# M868pld.net
KiCad netlist of a schematic drawn in EAGLE
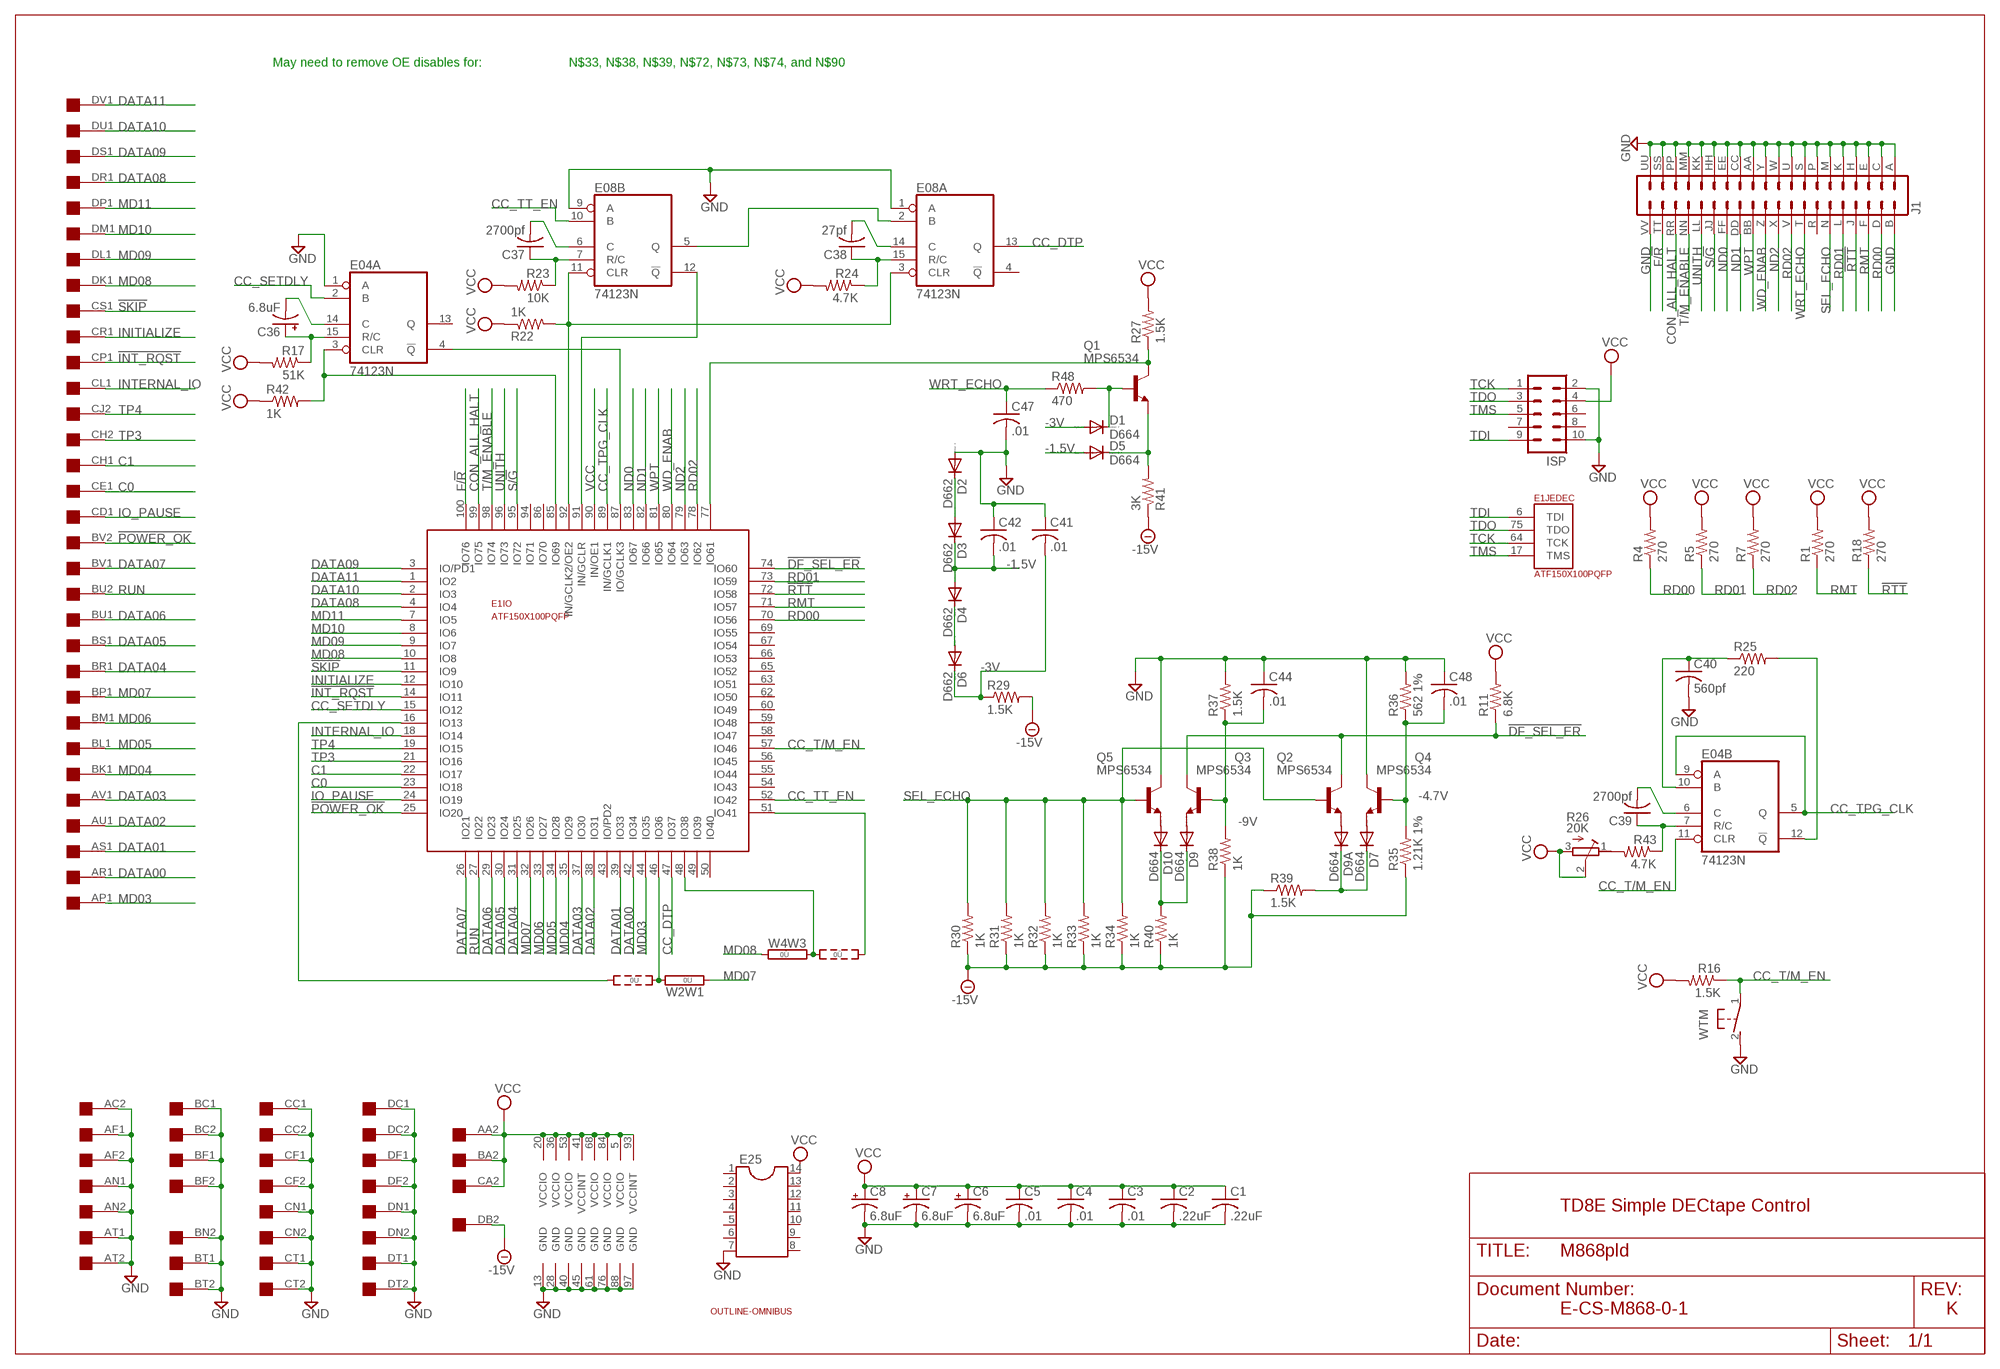
[diagram p0: schematic, sheet 1]

(export (version "E")
  (design (tool "Eeschema 10.0.6"))
  (components
    (comp (ref "C1")
      (value ".22uF")
      (footprint "eagle-import:C050-025X075")
      (libsource (lib "eagle-import") (part "C-US050-025X075"))
    )
    (comp (ref "C2")
      (value ".22uF")
      (footprint "eagle-import:C050-025X075")
      (libsource (lib "eagle-import") (part "C-US050-025X075"))
    )
    (comp (ref "C3")
      (value ".01")
      (footprint "eagle-import:C050-025X075")
      (libsource (lib "eagle-import") (part "C-US050-025X075"))
    )
    (comp (ref "C4")
      (value ".01")
      (footprint "eagle-import:C050-025X075")
      (libsource (lib "eagle-import") (part "C-US050-025X075"))
    )
    (comp (ref "C5")
      (value ".01")
      (footprint "eagle-import:C050-025X075")
      (libsource (lib "eagle-import") (part "C-US050-025X075"))
    )
    (comp (ref "C6")
      (value "6.8uF")
      (footprint "eagle-import:E12-8")
      (libsource (lib "eagle-import") (part "CPOL-USE20-8AXIAL"))
    )
    (comp (ref "C7")
      (value "6.8uF")
      (footprint "eagle-import:E12-8")
      (libsource (lib "eagle-import") (part "CPOL-USE20-8AXIAL"))
    )
    (comp (ref "C8")
      (value "6.8uF")
      (footprint "eagle-import:E12-8")
      (libsource (lib "eagle-import") (part "CPOL-USE20-8AXIAL"))
    )
    (comp (ref "C36")
      (value "6.8uF")
      (footprint "eagle-import:E12-8")
      (libsource (lib "eagle-import") (part "CPOL-USE20-8AXIAL"))
    )
    (comp (ref "C37")
      (value "2700pf")
      (footprint "eagle-import:C102-043X133")
      (libsource (lib "eagle-import") (part "C-US102-043X133"))
    )
    (comp (ref "C38")
      (value "27pf")
      (footprint "eagle-import:C050-025X075")
      (libsource (lib "eagle-import") (part "C-US050-025X075"))
    )
    (comp (ref "C39")
      (value "2700pf")
      (footprint "eagle-import:C102-043X133")
      (libsource (lib "eagle-import") (part "C-US102-043X133"))
    )
    (comp (ref "C40")
      (value "560pf")
      (footprint "eagle-import:C075-032X103")
      (libsource (lib "eagle-import") (part "C-US075-032X103"))
    )
    (comp (ref "C41")
      (value ".01")
      (footprint "eagle-import:C050-025X075")
      (libsource (lib "eagle-import") (part "C-US050-025X075"))
    )
    (comp (ref "C42")
      (value ".01")
      (footprint "eagle-import:C050-025X075")
      (libsource (lib "eagle-import") (part "C-US050-025X075"))
    )
    (comp (ref "C44")
      (value ".01")
      (footprint "eagle-import:C050-025X075")
      (libsource (lib "eagle-import") (part "C-US050-025X075"))
    )
    (comp (ref "C47")
      (value ".01")
      (footprint "eagle-import:C050-025X075")
      (libsource (lib "eagle-import") (part "C-US050-025X075"))
    )
    (comp (ref "C48")
      (value ".01")
      (footprint "eagle-import:C050-025X075")
      (libsource (lib "eagle-import") (part "C-US050-025X075"))
    )
    (comp (ref "D1")
      (value "D664")
      (footprint "eagle-import:DO35-10")
      (libsource (lib "eagle-import") (part "1N4148DO35-10"))
    )
    (comp (ref "D2")
      (value "D662")
      (footprint "eagle-import:DO35-10")
      (libsource (lib "eagle-import") (part "1N4148DO35-10"))
    )
    (comp (ref "D3")
      (value "D662")
      (footprint "eagle-import:DO35-10")
      (libsource (lib "eagle-import") (part "1N4148DO35-10"))
    )
    (comp (ref "D4")
      (value "D662")
      (footprint "eagle-import:DO35-10")
      (libsource (lib "eagle-import") (part "1N4148DO35-10"))
    )
    (comp (ref "D5")
      (value "D664")
      (footprint "eagle-import:DO35-10")
      (libsource (lib "eagle-import") (part "1N4148DO35-10"))
    )
    (comp (ref "D6")
      (value "D662")
      (footprint "eagle-import:DO35-10")
      (libsource (lib "eagle-import") (part "1N4148DO35-10"))
    )
    (comp (ref "D7")
      (value "D664")
      (footprint "eagle-import:DO35-10")
      (libsource (lib "eagle-import") (part "1N4148DO35-10"))
    )
    (comp (ref "D9")
      (value "D664")
      (footprint "eagle-import:DO35-10")
      (libsource (lib "eagle-import") (part "1N4148DO35-10"))
    )
    (comp (ref "D9A")
      (value "D664")
      (footprint "eagle-import:DO35-10")
      (libsource (lib "eagle-import") (part "1N4148DO35-10"))
    )
    (comp (ref "D10")
      (value "D664")
      (footprint "eagle-import:DO35-10")
      (libsource (lib "eagle-import") (part "1N4148DO35-10"))
    )
    (comp (ref "E1")
      (value "ATF150X100PQFP")
      (footprint "eagle-import:PQFP-100")
      (libsource (lib "eagle-import") (part "ATF150X100PQFP"))
    )
    (comp (ref "E04")
      (value "74123N")
      (footprint "eagle-import:DIL16")
      (libsource (lib "eagle-import") (part "74123N"))
    )
    (comp (ref "E08")
      (value "74123N")
      (footprint "eagle-import:DIL16")
      (libsource (lib "eagle-import") (part "74123N"))
    )
    (comp (ref "E25")
      (value "DIL14")
      (footprint "eagle-import:DIL14")
      (libsource (lib "eagle-import") (part "DIL14"))
    )
    (comp (ref "EDGE$3")
      (value "QUAD")
      (footprint "eagle-import:EDGE-CON8")
      (libsource (lib "eagle-import") (part "QUAD"))
    )
    (comp (ref "ISP")
      (value "MA05-2")
      (footprint "eagle-import:MA05-2")
      (libsource (lib "eagle-import") (part "MA05-2"))
    )
    (comp (ref "J1")
      (value "DEC40PINH")
      (footprint "eagle-import:DEC40PINH")
      (libsource (lib "eagle-import") (part "DEC40PINH"))
    )
    (comp (ref "Q1")
      (value "MPS6534")
      (footprint "eagle-import:TO5")
      (libsource (lib "eagle-import") (part "2N2219"))
    )
    (comp (ref "Q2")
      (value "MPS6534")
      (footprint "eagle-import:TO5")
      (libsource (lib "eagle-import") (part "2N2219"))
    )
    (comp (ref "Q3")
      (value "MPS6534")
      (footprint "eagle-import:TO5")
      (libsource (lib "eagle-import") (part "2N2219"))
    )
    (comp (ref "Q4")
      (value "MPS6534")
      (footprint "eagle-import:TO5")
      (libsource (lib "eagle-import") (part "2N2219"))
    )
    (comp (ref "Q5")
      (value "MPS6534")
      (footprint "eagle-import:TO5")
      (libsource (lib "eagle-import") (part "2N2219"))
    )
    (comp (ref "R1")
      (value "270")
      (footprint "eagle-import:0207_10")
      (libsource (lib "eagle-import") (part "R-US_0207/10"))
    )
    (comp (ref "R4")
      (value "270")
      (footprint "eagle-import:0207_10")
      (libsource (lib "eagle-import") (part "R-US_0207/10"))
    )
    (comp (ref "R5")
      (value "270")
      (footprint "eagle-import:0207_10")
      (libsource (lib "eagle-import") (part "R-US_0207/10"))
    )
    (comp (ref "R7")
      (value "270")
      (footprint "eagle-import:0207_10")
      (libsource (lib "eagle-import") (part "R-US_0207/10"))
    )
    (comp (ref "R11")
      (value "6.8K")
      (footprint "eagle-import:0207_10")
      (libsource (lib "eagle-import") (part "R-US_0207/10"))
    )
    (comp (ref "R16")
      (value "1.5K")
      (footprint "eagle-import:0207_10")
      (libsource (lib "eagle-import") (part "R-US_0207/10"))
    )
    (comp (ref "R17")
      (value "51K")
      (footprint "eagle-import:0207_10")
      (libsource (lib "eagle-import") (part "R-US_0207/10"))
    )
    (comp (ref "R18")
      (value "270")
      (footprint "eagle-import:0207_10")
      (libsource (lib "eagle-import") (part "R-US_0207/10"))
    )
    (comp (ref "R22")
      (value "1K")
      (footprint "eagle-import:0207_10")
      (libsource (lib "eagle-import") (part "R-US_0207/10"))
    )
    (comp (ref "R23")
      (value "10K")
      (footprint "eagle-import:0207_10")
      (libsource (lib "eagle-import") (part "R-US_0207/10"))
    )
    (comp (ref "R24")
      (value "4.7K")
      (footprint "eagle-import:0207_10")
      (libsource (lib "eagle-import") (part "R-US_0207/10"))
    )
    (comp (ref "R25")
      (value "220")
      (footprint "eagle-import:0207_10")
      (libsource (lib "eagle-import") (part "R-US_0207/10"))
    )
    (comp (ref "R26")
      (value "20K")
      (footprint "eagle-import:3006Y")
      (libsource (lib "eagle-import") (part "275P"))
    )
    (comp (ref "R27")
      (value "1.5K")
      (footprint "eagle-import:0207_10")
      (libsource (lib "eagle-import") (part "R-US_0207/10"))
    )
    (comp (ref "R29")
      (value "1.5K")
      (footprint "eagle-import:0207_10")
      (libsource (lib "eagle-import") (part "R-US_0207/10"))
    )
    (comp (ref "R30")
      (value "1K")
      (footprint "eagle-import:0207_10")
      (libsource (lib "eagle-import") (part "R-US_0207/10"))
    )
    (comp (ref "R31")
      (value "1K")
      (footprint "eagle-import:0207_10")
      (libsource (lib "eagle-import") (part "R-US_0207/10"))
    )
    (comp (ref "R32")
      (value "1K")
      (footprint "eagle-import:0207_10")
      (libsource (lib "eagle-import") (part "R-US_0207/10"))
    )
    (comp (ref "R33")
      (value "1K")
      (footprint "eagle-import:0207_10")
      (libsource (lib "eagle-import") (part "R-US_0207/10"))
    )
    (comp (ref "R34")
      (value "1K")
      (footprint "eagle-import:0207_10")
      (libsource (lib "eagle-import") (part "R-US_0207/10"))
    )
    (comp (ref "R35")
      (value "1.21K 1%")
      (footprint "eagle-import:0207_15")
      (libsource (lib "eagle-import") (part "R-US_0207/15"))
    )
    (comp (ref "R36")
      (value "562 1%")
      (footprint "eagle-import:0207_15")
      (libsource (lib "eagle-import") (part "R-US_0207/15"))
    )
    (comp (ref "R37")
      (value "1.5K")
      (footprint "eagle-import:0207_10")
      (libsource (lib "eagle-import") (part "R-US_0207/10"))
    )
    (comp (ref "R38")
      (value "1K")
      (footprint "eagle-import:0207_10")
      (libsource (lib "eagle-import") (part "R-US_0207/10"))
    )
    (comp (ref "R39")
      (value "1.5K")
      (footprint "eagle-import:0207_10")
      (libsource (lib "eagle-import") (part "R-US_0207/10"))
    )
    (comp (ref "R40")
      (value "1K")
      (footprint "eagle-import:0207_10")
      (libsource (lib "eagle-import") (part "R-US_0207/10"))
    )
    (comp (ref "R41")
      (value "3K")
      (footprint "eagle-import:0207_10")
      (libsource (lib "eagle-import") (part "R-US_0207/10"))
    )
    (comp (ref "R42")
      (value "1K")
      (footprint "eagle-import:0207_10")
      (libsource (lib "eagle-import") (part "R-US_0207/10"))
    )
    (comp (ref "R43")
      (value "4.7K")
      (footprint "eagle-import:0207_10")
      (libsource (lib "eagle-import") (part "R-US_0207/10"))
    )
    (comp (ref "R48")
      (value "470")
      (footprint "eagle-import:0207_10")
      (libsource (lib "eagle-import") (part "R-US_0207/10"))
    )
    (comp (ref "U$1")
      (value "OUTLINE-OMNIBUS")
      (footprint "eagle-import:OMNIBUS")
      (libsource (lib "eagle-import") (part "OUTLINE-OMNIBUS"))
    )
    (comp (ref "W2W1")
      (value "0R2")
      (footprint "eagle-import:0R2_10")
      (libsource (lib "eagle-import") (part "0R2"))
    )
    (comp (ref "W4W3")
      (value "0R2")
      (footprint "eagle-import:0R2_10")
      (libsource (lib "eagle-import") (part "0R2"))
    )
    (comp (ref "WTM")
      (value "31-XX")
      (footprint "eagle-import:B3F-31XX")
      (fields (field (name "MPN") "B3F-3100"))
      (libsource (lib "eagle-import") (part "31-XX"))
    )
  )
  (nets
    (net (code "1") (name "-15V") (class "Default")
      (node (ref "EDGE$3") (pin "DB2") (pinfunction "1_DB2") (pintype "bidirectional"))
      (node (ref "R29") (pin "2") (pinfunction "2_2") (pintype "passive"))
      (node (ref "R30") (pin "1") (pinfunction "1_1") (pintype "passive"))
      (node (ref "R31") (pin "1") (pinfunction "1_1") (pintype "passive"))
      (node (ref "R32") (pin "1") (pinfunction "1_1") (pintype "passive"))
      (node (ref "R33") (pin "1") (pinfunction "1_1") (pintype "passive"))
      (node (ref "R34") (pin "1") (pinfunction "1_1") (pintype "passive"))
      (node (ref "R35") (pin "1") (pinfunction "1_1") (pintype "passive"))
      (node (ref "R38") (pin "1") (pinfunction "1_1") (pintype "passive"))
      (node (ref "R39") (pin "1") (pinfunction "1_1") (pintype "passive"))
      (node (ref "R40") (pin "1") (pinfunction "1_1") (pintype "passive"))
      (node (ref "R41") (pin "1") (pinfunction "1_1") (pintype "passive"))
    )
    (net (code "2") (name "/-1.5V") (class "Default")
      (node (ref "C42") (pin "2") (pinfunction "2_2") (pintype "passive"))
      (node (ref "D3") (pin "C") (pinfunction "C_C") (pintype "passive"))
      (node (ref "D4") (pin "A") (pinfunction "A_A") (pintype "passive"))
      (node (ref "D5") (pin "A") (pinfunction "A_A") (pintype "passive"))
    )
    (net (code "3") (name "/-3V") (class "Default")
      (node (ref "C41") (pin "2") (pinfunction "2_2") (pintype "passive"))
      (node (ref "D1") (pin "A") (pinfunction "A_A") (pintype "passive"))
      (node (ref "D6") (pin "C") (pinfunction "C_C") (pintype "passive"))
      (node (ref "R29") (pin "1") (pinfunction "1_1") (pintype "passive"))
    )
    (net (code "4") (name "/-4.7V") (class "Default")
      (node (ref "C48") (pin "2") (pinfunction "2_2") (pintype "passive"))
      (node (ref "Q4") (pin "2") (pinfunction "B_2") (pintype "passive"))
      (node (ref "R35") (pin "2") (pinfunction "2_2") (pintype "passive"))
      (node (ref "R36") (pin "1") (pinfunction "1_1") (pintype "passive"))
    )
    (net (code "5") (name "/-9V") (class "Default")
      (node (ref "C44") (pin "2") (pinfunction "2_2") (pintype "passive"))
      (node (ref "Q3") (pin "2") (pinfunction "B_2") (pintype "passive"))
      (node (ref "R37") (pin "1") (pinfunction "1_1") (pintype "passive"))
      (node (ref "R38") (pin "2") (pinfunction "2_2") (pintype "passive"))
    )
    (net (code "6") (name "/C0") (class "Default")
      (node (ref "E1") (pin "23") (pinfunction "IO18_23") (pintype "bidirectional"))
      (node (ref "EDGE$3") (pin "CE1") (pinfunction "1_CE1") (pintype "bidirectional"))
    )
    (net (code "7") (name "/C1") (class "Default")
      (node (ref "E1") (pin "22") (pinfunction "IO17_22") (pintype "bidirectional"))
      (node (ref "EDGE$3") (pin "CH1") (pinfunction "1_CH1") (pintype "bidirectional"))
    )
    (net (code "8") (name "/CC_DTP") (class "Default")
      (node (ref "E08") (pin "13") (pinfunction "Q_13") (pintype "output"))
      (node (ref "E1") (pin "47") (pinfunction "IO37_47") (pintype "bidirectional"))
    )
    (net (code "9") (name "/CC_SETDLY") (class "Default")
      (node (ref "E04") (pin "2") (pinfunction "B_2") (pintype "input"))
      (node (ref "E1") (pin "15") (pinfunction "IO12_15") (pintype "bidirectional"))
    )
    (net (code "10") (name "/CC_TPG_CLK") (class "Default")
      (node (ref "E04") (pin "5") (pinfunction "Q_5") (pintype "output"))
      (node (ref "E04") (pin "9") (pinfunction "A_9") (pintype "input"))
      (node (ref "E1") (pin "89") (pinfunction "IN/GCLK1_89") (pintype "input"))
    )
    (net (code "11") (name "/CC_TT_EN") (class "Default")
      (node (ref "E08") (pin "10") (pinfunction "B_10") (pintype "input"))
      (node (ref "E1") (pin "52") (pinfunction "IO42_52") (pintype "bidirectional"))
    )
    (net (code "12") (name "/CC_T{slash}M_EN") (class "Default")
      (node (ref "E04") (pin "11") (pinfunction "CLR_11") (pintype "input"))
      (node (ref "E1") (pin "57") (pinfunction "IO46_57") (pintype "bidirectional"))
      (node (ref "R16") (pin "1") (pinfunction "1_1") (pintype "passive"))
      (node (ref "WTM") (pin "1") (pinfunction "P_1") (pintype "passive"))
    )
    (net (code "13") (name "/CON_ALL_HALT") (class "Default")
      (node (ref "E1") (pin "99") (pinfunction "IO75_99") (pintype "bidirectional"))
      (node (ref "J1") (pin "RR") (pinfunction "36_RR") (pintype "bidirectional"))
    )
    (net (code "14") (name "/DATA00") (class "Default")
      (node (ref "E1") (pin "42") (pinfunction "IO34_42") (pintype "bidirectional"))
      (node (ref "EDGE$3") (pin "AR1") (pinfunction "1_AR1") (pintype "bidirectional"))
    )
    (net (code "15") (name "/DATA01") (class "Default")
      (node (ref "E1") (pin "39") (pinfunction "IO33_39") (pintype "bidirectional"))
      (node (ref "EDGE$3") (pin "AS1") (pinfunction "1_AS1") (pintype "bidirectional"))
    )
    (net (code "16") (name "/DATA02") (class "Default")
      (node (ref "E1") (pin "38") (pinfunction "IO31_38") (pintype "bidirectional"))
      (node (ref "EDGE$3") (pin "AU1") (pinfunction "1_AU1") (pintype "bidirectional"))
    )
    (net (code "17") (name "/DATA03") (class "Default")
      (node (ref "E1") (pin "37") (pinfunction "IO30_37") (pintype "bidirectional"))
      (node (ref "EDGE$3") (pin "AV1") (pinfunction "1_AV1") (pintype "bidirectional"))
    )
    (net (code "18") (name "/DATA04") (class "Default")
      (node (ref "E1") (pin "31") (pinfunction "IO25_31") (pintype "bidirectional"))
      (node (ref "EDGE$3") (pin "BR1") (pinfunction "1_BR1") (pintype "bidirectional"))
    )
    (net (code "19") (name "/DATA05") (class "Default")
      (node (ref "E1") (pin "30") (pinfunction "IO24_30") (pintype "bidirectional"))
      (node (ref "EDGE$3") (pin "BS1") (pinfunction "1_BS1") (pintype "bidirectional"))
    )
    (net (code "20") (name "/DATA06") (class "Default")
      (node (ref "E1") (pin "29") (pinfunction "IO23_29") (pintype "bidirectional"))
      (node (ref "EDGE$3") (pin "BU1") (pinfunction "1_BU1") (pintype "bidirectional"))
    )
    (net (code "21") (name "/DATA07") (class "Default")
      (node (ref "E1") (pin "26") (pinfunction "IO21_26") (pintype "bidirectional"))
      (node (ref "EDGE$3") (pin "BV1") (pinfunction "1_BV1") (pintype "bidirectional"))
    )
    (net (code "22") (name "/DATA08") (class "Default")
      (node (ref "E1") (pin "4") (pinfunction "IO4_4") (pintype "bidirectional"))
      (node (ref "EDGE$3") (pin "DR1") (pinfunction "1_DR1") (pintype "bidirectional"))
    )
    (net (code "23") (name "/DATA09") (class "Default")
      (node (ref "E1") (pin "3") (pinfunction "IO/PD1_3") (pintype "bidirectional"))
      (node (ref "EDGE$3") (pin "DS1") (pinfunction "1_DS1") (pintype "bidirectional"))
    )
    (net (code "24") (name "/DATA10") (class "Default")
      (node (ref "E1") (pin "2") (pinfunction "IO3_2") (pintype "bidirectional"))
      (node (ref "EDGE$3") (pin "DU1") (pinfunction "1_DU1") (pintype "bidirectional"))
    )
    (net (code "25") (name "/DATA11") (class "Default")
      (node (ref "E1") (pin "1") (pinfunction "IO2_1") (pintype "bidirectional"))
      (node (ref "EDGE$3") (pin "DV1") (pinfunction "1_DV1") (pintype "bidirectional"))
    )
    (net (code "26") (name "/F{slash}~{R}") (class "Default")
      (node (ref "E1") (pin "100") (pinfunction "IO76_100") (pintype "bidirectional"))
      (node (ref "J1") (pin "TT") (pinfunction "38_TT") (pintype "bidirectional"))
    )
    (net (code "27") (name "/INITIALIZE") (class "Default")
      (node (ref "E1") (pin "12") (pinfunction "IO10_12") (pintype "bidirectional"))
      (node (ref "EDGE$3") (pin "CR1") (pinfunction "1_CR1") (pintype "bidirectional"))
    )
    (net (code "28") (name "/INTERNAL_IO") (class "Default")
      (node (ref "E1") (pin "18") (pinfunction "IO14_18") (pintype "bidirectional"))
      (node (ref "EDGE$3") (pin "CL1") (pinfunction "1_CL1") (pintype "bidirectional"))
    )
    (net (code "29") (name "/IO_PAUSE") (class "Default")
      (node (ref "E1") (pin "24") (pinfunction "IO19_24") (pintype "bidirectional"))
      (node (ref "EDGE$3") (pin "CD1") (pinfunction "1_CD1") (pintype "bidirectional"))
    )
    (net (code "30") (name "/MD03") (class "Default")
      (node (ref "E1") (pin "44") (pinfunction "IO35_44") (pintype "bidirectional"))
      (node (ref "EDGE$3") (pin "AP1") (pinfunction "1_AP1") (pintype "bidirectional"))
    )
    (net (code "31") (name "/MD04") (class "Default")
      (node (ref "E1") (pin "35") (pinfunction "IO29_35") (pintype "bidirectional"))
      (node (ref "EDGE$3") (pin "BK1") (pinfunction "1_BK1") (pintype "bidirectional"))
    )
    (net (code "32") (name "/MD05") (class "Default")
      (node (ref "E1") (pin "34") (pinfunction "IO28_34") (pintype "bidirectional"))
      (node (ref "EDGE$3") (pin "BL1") (pinfunction "1_BL1") (pintype "bidirectional"))
    )
    (net (code "33") (name "/MD06") (class "Default")
      (node (ref "E1") (pin "33") (pinfunction "IO27_33") (pintype "bidirectional"))
      (node (ref "EDGE$3") (pin "BM1") (pinfunction "1_BM1") (pintype "bidirectional"))
    )
    (net (code "34") (name "/MD07") (class "Default")
      (node (ref "E1") (pin "32") (pinfunction "IO26_32") (pintype "bidirectional"))
      (node (ref "EDGE$3") (pin "BP1") (pinfunction "1_BP1") (pintype "bidirectional"))
      (node (ref "W2W1") (pin "1") (pinfunction "1_1") (pintype "passive"))
    )
    (net (code "35") (name "/MD08") (class "Default")
      (node (ref "E1") (pin "10") (pinfunction "IO8_10") (pintype "bidirectional"))
      (node (ref "EDGE$3") (pin "DK1") (pinfunction "1_DK1") (pintype "bidirectional"))
      (node (ref "W4W3") (pin "1") (pinfunction "1_1") (pintype "passive"))
    )
    (net (code "36") (name "/MD09") (class "Default")
      (node (ref "E1") (pin "9") (pinfunction "IO7_9") (pintype "bidirectional"))
      (node (ref "EDGE$3") (pin "DL1") (pinfunction "1_DL1") (pintype "bidirectional"))
    )
    (net (code "37") (name "/MD10") (class "Default")
      (node (ref "E1") (pin "8") (pinfunction "IO6_8") (pintype "bidirectional"))
      (node (ref "EDGE$3") (pin "DM1") (pinfunction "1_DM1") (pintype "bidirectional"))
    )
    (net (code "38") (name "/MD11") (class "Default")
      (node (ref "E1") (pin "7") (pinfunction "IO5_7") (pintype "bidirectional"))
      (node (ref "EDGE$3") (pin "DP1") (pinfunction "1_DP1") (pintype "bidirectional"))
    )
    (net (code "39") (name "/ND0") (class "Default")
      (node (ref "E1") (pin "83") (pinfunction "IO67_83") (pintype "bidirectional"))
      (node (ref "J1") (pin "FF") (pinfunction "28_FF") (pintype "bidirectional"))
    )
    (net (code "40") (name "/ND1") (class "Default")
      (node (ref "E1") (pin "82") (pinfunction "IO66_82") (pintype "bidirectional"))
      (node (ref "J1") (pin "DD") (pinfunction "26_DD") (pintype "bidirectional"))
    )
    (net (code "41") (name "/ND2") (class "Default")
      (node (ref "E1") (pin "79") (pinfunction "IO63_79") (pintype "bidirectional"))
      (node (ref "J1") (pin "X") (pinfunction "20_X") (pintype "bidirectional"))
    )
    (net (code "42") (name "/RD00") (class "Default")
      (node (ref "E1") (pin "70") (pinfunction "IO56_70") (pintype "bidirectional"))
      (node (ref "J1") (pin "D") (pinfunction "4_D") (pintype "bidirectional"))
      (node (ref "R4") (pin "1") (pinfunction "1_1") (pintype "passive"))
    )
    (net (code "43") (name "/RD01") (class "Default")
      (node (ref "E1") (pin "73") (pinfunction "IO59_73") (pintype "bidirectional"))
      (node (ref "J1") (pin "L") (pinfunction "10_L") (pintype "bidirectional"))
      (node (ref "R5") (pin "1") (pinfunction "1_1") (pintype "passive"))
    )
    (net (code "44") (name "/RD02") (class "Default")
      (node (ref "E1") (pin "78") (pinfunction "IO62_78") (pintype "bidirectional"))
      (node (ref "J1") (pin "V") (pinfunction "18_V") (pintype "bidirectional"))
      (node (ref "R7") (pin "1") (pinfunction "1_1") (pintype "passive"))
    )
    (net (code "45") (name "/RMT") (class "Default")
      (node (ref "E1") (pin "71") (pinfunction "IO57_71") (pintype "bidirectional"))
      (node (ref "J1") (pin "F") (pinfunction "6_F") (pintype "bidirectional"))
      (node (ref "R1") (pin "1") (pinfunction "1_1") (pintype "passive"))
    )
    (net (code "46") (name "/RUN") (class "Default")
      (node (ref "E1") (pin "27") (pinfunction "IO22_27") (pintype "bidirectional"))
      (node (ref "EDGE$3") (pin "BU2") (pinfunction "1_BU2") (pintype "bidirectional"))
    )
    (net (code "47") (name "/SEL_ECHO") (class "Default")
      (node (ref "J1") (pin "N") (pinfunction "12_N") (pintype "bidirectional"))
      (node (ref "Q2") (pin "2") (pinfunction "B_2") (pintype "passive"))
      (node (ref "Q5") (pin "2") (pinfunction "B_2") (pintype "passive"))
      (node (ref "R30") (pin "2") (pinfunction "2_2") (pintype "passive"))
      (node (ref "R31") (pin "2") (pinfunction "2_2") (pintype "passive"))
      (node (ref "R32") (pin "2") (pinfunction "2_2") (pintype "passive"))
      (node (ref "R33") (pin "2") (pinfunction "2_2") (pintype "passive"))
      (node (ref "R34") (pin "2") (pinfunction "2_2") (pintype "passive"))
    )
    (net (code "48") (name "/S{slash}~{G}") (class "Default")
      (node (ref "E1") (pin "95") (pinfunction "IO72_95") (pintype "bidirectional"))
      (node (ref "J1") (pin "JJ") (pinfunction "30_JJ") (pintype "bidirectional"))
    )
    (net (code "49") (name "/TCK") (class "Default")
      (node (ref "E1") (pin "64") (pinfunction "TCK_64") (pintype "bidirectional"))
      (node (ref "ISP") (pin "1") (pinfunction "1_1") (pintype "passive"))
    )
    (net (code "50") (name "/TDI") (class "Default")
      (node (ref "E1") (pin "6") (pinfunction "TDI_6") (pintype "bidirectional"))
      (node (ref "ISP") (pin "9") (pinfunction "9_9") (pintype "passive"))
    )
    (net (code "51") (name "/TDO") (class "Default")
      (node (ref "E1") (pin "75") (pinfunction "TDO_75") (pintype "bidirectional"))
      (node (ref "ISP") (pin "3") (pinfunction "3_3") (pintype "passive"))
    )
    (net (code "52") (name "/TMS") (class "Default")
      (node (ref "E1") (pin "17") (pinfunction "TMS_17") (pintype "bidirectional"))
      (node (ref "ISP") (pin "5") (pinfunction "5_5") (pintype "passive"))
    )
    (net (code "53") (name "/TP3") (class "Default")
      (node (ref "E1") (pin "21") (pinfunction "IO16_21") (pintype "bidirectional"))
      (node (ref "EDGE$3") (pin "CH2") (pinfunction "1_CH2") (pintype "bidirectional"))
    )
    (net (code "54") (name "/TP4") (class "Default")
      (node (ref "E1") (pin "19") (pinfunction "IO15_19") (pintype "bidirectional"))
      (node (ref "EDGE$3") (pin "CJ2") (pinfunction "1_CJ2") (pintype "bidirectional"))
    )
    (net (code "55") (name "/T{slash}M_ENABLE") (class "Default")
      (node (ref "E1") (pin "98") (pinfunction "IO74_98") (pintype "bidirectional"))
      (node (ref "J1") (pin "NN") (pinfunction "34_NN") (pintype "bidirectional"))
    )
    (net (code "56") (name "/UNITH") (class "Default")
      (node (ref "E1") (pin "96") (pinfunction "IO73_96") (pintype "bidirectional"))
      (node (ref "J1") (pin "LL") (pinfunction "32_LL") (pintype "bidirectional"))
    )
    (net (code "57") (name "/WD_ENAB") (class "Default")
      (node (ref "E1") (pin "80") (pinfunction "IO64_80") (pintype "bidirectional"))
      (node (ref "J1") (pin "Z") (pinfunction "22_Z") (pintype "bidirectional"))
    )
    (net (code "58") (name "/WPT") (class "Default")
      (node (ref "E1") (pin "81") (pinfunction "IO65_81") (pintype "bidirectional"))
      (node (ref "J1") (pin "BB") (pinfunction "24_BB") (pintype "bidirectional"))
    )
    (net (code "59") (name "/WRT_ECHO") (class "Default")
      (node (ref "C47") (pin "1") (pinfunction "1_1") (pintype "passive"))
      (node (ref "J1") (pin "T") (pinfunction "16_T") (pintype "bidirectional"))
      (node (ref "R48") (pin "1") (pinfunction "1_1") (pintype "passive"))
    )
    (net (code "60") (name "/~{DF_SEL_ER}") (class "Default")
      (node (ref "E1") (pin "74") (pinfunction "IO60_74") (pintype "bidirectional"))
      (node (ref "Q2") (pin "3") (pinfunction "C_3") (pintype "passive"))
      (node (ref "Q3") (pin "3") (pinfunction "C_3") (pintype "passive"))
      (node (ref "R11") (pin "1") (pinfunction "1_1") (pintype "passive"))
    )
    (net (code "61") (name "/~{INT_RQST}") (class "Default")
      (node (ref "E1") (pin "14") (pinfunction "IO11_14") (pintype "bidirectional"))
      (node (ref "EDGE$3") (pin "CP1") (pinfunction "1_CP1") (pintype "bidirectional"))
    )
    (net (code "62") (name "/~{POWER_OK}") (class "Default")
      (node (ref "E1") (pin "25") (pinfunction "IO20_25") (pintype "bidirectional"))
      (node (ref "EDGE$3") (pin "BV2") (pinfunction "1_BV2") (pintype "bidirectional"))
    )
    (net (code "63") (name "/~{RTT}") (class "Default")
      (node (ref "E1") (pin "72") (pinfunction "IO58_72") (pintype "bidirectional"))
      (node (ref "J1") (pin "J") (pinfunction "8_J") (pintype "bidirectional"))
      (node (ref "R18") (pin "1") (pinfunction "1_1") (pintype "passive"))
    )
    (net (code "64") (name "/~{SKIP}") (class "Default")
      (node (ref "E1") (pin "11") (pinfunction "IO9_11") (pintype "bidirectional"))
      (node (ref "EDGE$3") (pin "CS1") (pinfunction "1_CS1") (pintype "bidirectional"))
    )
    (net (code "65") (name "GND") (class "Default")
      (node (ref "C1") (pin "2") (pinfunction "2_2") (pintype "passive"))
      (node (ref "C2") (pin "2") (pinfunction "2_2") (pintype "passive"))
      (node (ref "C3") (pin "2") (pinfunction "2_2") (pintype "passive"))
      (node (ref "C4") (pin "2") (pinfunction "2_2") (pintype "passive"))
      (node (ref "C40") (pin "2") (pinfunction "2_2") (pintype "passive"))
      (node (ref "C41") (pin "1") (pinfunction "1_1") (pintype "passive"))
      (node (ref "C42") (pin "1") (pinfunction "1_1") (pintype "passive"))
      (node (ref "C44") (pin "1") (pinfunction "1_1") (pintype "passive"))
      (node (ref "C47") (pin "2") (pinfunction "2_2") (pintype "passive"))
      (node (ref "C48") (pin "1") (pinfunction "1_1") (pintype "passive"))
      (node (ref "C5") (pin "2") (pinfunction "2_2") (pintype "passive"))
      (node (ref "C6") (pin "-") (pinfunction "-_-") (pintype "passive"))
      (node (ref "C7") (pin "-") (pinfunction "-_-") (pintype "passive"))
      (node (ref "C8") (pin "-") (pinfunction "-_-") (pintype "passive"))
      (node (ref "D2") (pin "A") (pinfunction "A_A") (pintype "passive"))
      (node (ref "E04") (pin "1") (pinfunction "A_1") (pintype "input"))
      (node (ref "E08") (pin "1") (pinfunction "A_1") (pintype "input"))
      (node (ref "E08") (pin "9") (pinfunction "A_9") (pintype "input"))
      (node (ref "E1") (pin "13") (pinfunction "GND_13") (pintype "power_in"))
      (node (ref "E1") (pin "28") (pinfunction "GND_28") (pintype "power_in"))
      (node (ref "E1") (pin "40") (pinfunction "GND_40") (pintype "power_in"))
      (node (ref "E1") (pin "45") (pinfunction "GND_45") (pintype "power_in"))
      (node (ref "E1") (pin "61") (pinfunction "GND_61") (pintype "power_in"))
      (node (ref "E1") (pin "76") (pinfunction "GND_76") (pintype "power_in"))
      (node (ref "E1") (pin "88") (pinfunction "GND_88") (pintype "power_in"))
      (node (ref "E1") (pin "97") (pinfunction "GND_97") (pintype "power_in"))
      (node (ref "E25") (pin "7") (pinfunction "7_7") (pintype "passive"))
      (node (ref "EDGE$3") (pin "AC2") (pinfunction "1_AC2") (pintype "bidirectional"))
      (node (ref "EDGE$3") (pin "AF1") (pinfunction "1_AF1") (pintype "bidirectional"))
      (node (ref "EDGE$3") (pin "AF2") (pinfunction "1_AF2") (pintype "bidirectional"))
      (node (ref "EDGE$3") (pin "AN1") (pinfunction "1_AN1") (pintype "bidirectional"))
      (node (ref "EDGE$3") (pin "AN2") (pinfunction "1_AN2") (pintype "bidirectional"))
      (node (ref "EDGE$3") (pin "AT1") (pinfunction "1_AT1") (pintype "bidirectional"))
      (node (ref "EDGE$3") (pin "AT2") (pinfunction "1_AT2") (pintype "bidirectional"))
      (node (ref "EDGE$3") (pin "BC1") (pinfunction "1_BC1") (pintype "bidirectional"))
      (node (ref "EDGE$3") (pin "BC2") (pinfunction "1_BC2") (pintype "bidirectional"))
      (node (ref "EDGE$3") (pin "BF1") (pinfunction "1_BF1") (pintype "bidirectional"))
      (node (ref "EDGE$3") (pin "BF2") (pinfunction "1_BF2") (pintype "bidirectional"))
      (node (ref "EDGE$3") (pin "BN2") (pinfunction "1_BN2") (pintype "bidirectional"))
      (node (ref "EDGE$3") (pin "BT1") (pinfunction "1_BT1") (pintype "bidirectional"))
      (node (ref "EDGE$3") (pin "BT2") (pinfunction "1_BT2") (pintype "bidirectional"))
      (node (ref "EDGE$3") (pin "CC1") (pinfunction "1_CC1") (pintype "bidirectional"))
      (node (ref "EDGE$3") (pin "CC2") (pinfunction "1_CC2") (pintype "bidirectional"))
      (node (ref "EDGE$3") (pin "CF1") (pinfunction "1_CF1") (pintype "bidirectional"))
      (node (ref "EDGE$3") (pin "CF2") (pinfunction "1_CF2") (pintype "bidirectional"))
      (node (ref "EDGE$3") (pin "CN1") (pinfunction "1_CN1") (pintype "bidirectional"))
      (node (ref "EDGE$3") (pin "CN2") (pinfunction "1_CN2") (pintype "bidirectional"))
      (node (ref "EDGE$3") (pin "CT1") (pinfunction "1_CT1") (pintype "bidirectional"))
      (node (ref "EDGE$3") (pin "CT2") (pinfunction "1_CT2") (pintype "bidirectional"))
      (node (ref "EDGE$3") (pin "DC1") (pinfunction "1_DC1") (pintype "bidirectional"))
      (node (ref "EDGE$3") (pin "DC2") (pinfunction "1_DC2") (pintype "bidirectional"))
      (node (ref "EDGE$3") (pin "DF1") (pinfunction "1_DF1") (pintype "bidirectional"))
      (node (ref "EDGE$3") (pin "DF2") (pinfunction "1_DF2") (pintype "bidirectional"))
      (node (ref "EDGE$3") (pin "DN1") (pinfunction "1_DN1") (pintype "bidirectional"))
      (node (ref "EDGE$3") (pin "DN2") (pinfunction "1_DN2") (pintype "bidirectional"))
      (node (ref "EDGE$3") (pin "DT1") (pinfunction "1_DT1") (pintype "bidirectional"))
      (node (ref "EDGE$3") (pin "DT2") (pinfunction "1_DT2") (pintype "bidirectional"))
      (node (ref "ISP") (pin "10") (pinfunction "10_10") (pintype "passive"))
      (node (ref "ISP") (pin "2") (pinfunction "2_2") (pintype "passive"))
      (node (ref "J1") (pin "A") (pinfunction "1_A") (pintype "bidirectional"))
      (node (ref "J1") (pin "AA") (pinfunction "23_AA") (pintype "bidirectional"))
      (node (ref "J1") (pin "B") (pinfunction "2_B") (pintype "bidirectional"))
      (node (ref "J1") (pin "C") (pinfunction "3_C") (pintype "bidirectional"))
      (node (ref "J1") (pin "CC") (pinfunction "25_CC") (pintype "bidirectional"))
      (node (ref "J1") (pin "E") (pinfunction "5_E") (pintype "bidirectional"))
      (node (ref "J1") (pin "EE") (pinfunction "27_EE") (pintype "bidirectional"))
      (node (ref "J1") (pin "H") (pinfunction "7_H") (pintype "bidirectional"))
      (node (ref "J1") (pin "HH") (pinfunction "29_HH") (pintype "bidirectional"))
      (node (ref "J1") (pin "K") (pinfunction "9_K") (pintype "bidirectional"))
      (node (ref "J1") (pin "KK") (pinfunction "31_KK") (pintype "bidirectional"))
      (node (ref "J1") (pin "M") (pinfunction "11_M") (pintype "bidirectional"))
      (node (ref "J1") (pin "MM") (pinfunction "33_MM") (pintype "bidirectional"))
      (node (ref "J1") (pin "P") (pinfunction "13_P") (pintype "bidirectional"))
      (node (ref "J1") (pin "PP") (pinfunction "35_PP") (pintype "bidirectional"))
      (node (ref "J1") (pin "S") (pinfunction "15_S") (pintype "bidirectional"))
      (node (ref "J1") (pin "SS") (pinfunction "37_SS") (pintype "bidirectional"))
      (node (ref "J1") (pin "U") (pinfunction "17_U") (pintype "bidirectional"))
      (node (ref "J1") (pin "UU") (pinfunction "39_UU") (pintype "bidirectional"))
      (node (ref "J1") (pin "VV") (pinfunction "40_VV") (pintype "bidirectional"))
      (node (ref "J1") (pin "W") (pinfunction "19_W") (pintype "bidirectional"))
      (node (ref "J1") (pin "Y") (pinfunction "21_Y") (pintype "bidirectional"))
      (node (ref "Q4") (pin "3") (pinfunction "C_3") (pintype "passive"))
      (node (ref "Q5") (pin "3") (pinfunction "C_3") (pintype "passive"))
      (node (ref "R36") (pin "2") (pinfunction "2_2") (pintype "passive"))
      (node (ref "R37") (pin "2") (pinfunction "2_2") (pintype "passive"))
      (node (ref "WTM") (pin "2") (pinfunction "S_2") (pintype "passive"))
    )
    (net (code "66") (name "Net-(D2-PadC)") (class "Default")
      (node (ref "D2") (pin "C") (pinfunction "C_C") (pintype "passive"))
      (node (ref "D3") (pin "A") (pinfunction "A_A") (pintype "passive"))
    )
    (net (code "67") (name "Net-(D4-PadC)") (class "Default")
      (node (ref "D4") (pin "C") (pinfunction "C_C") (pintype "passive"))
      (node (ref "D6") (pin "A") (pinfunction "A_A") (pintype "passive"))
    )
    (net (code "68") (name "Net-(D7-PadC)") (class "Default")
      (node (ref "D7") (pin "C") (pinfunction "C_C") (pintype "passive"))
      (node (ref "D9A") (pin "C") (pinfunction "C_C") (pintype "passive"))
      (node (ref "R39") (pin "2") (pinfunction "2_2") (pintype "passive"))
    )
    (net (code "69") (name "Net-(D10-PadC)") (class "Default")
      (node (ref "D10") (pin "C") (pinfunction "C_C") (pintype "passive"))
      (node (ref "D9") (pin "C") (pinfunction "C_C") (pintype "passive"))
      (node (ref "R40") (pin "2") (pinfunction "2_2") (pintype "passive"))
    )
    (net (code "70") (name "Net-(E1Q-IO13)") (class "Default")
      (node (ref "E1") (pin "16") (pinfunction "IO13_16") (pintype "bidirectional"))
      (node (ref "W2W1") (pin "3") (pinfunction "3_3") (pintype "passive"))
    )
    (net (code "71") (name "Net-(E1Q-IO36)") (class "Default")
      (node (ref "E1") (pin "46") (pinfunction "IO36_46") (pintype "bidirectional"))
      (node (ref "W2W1") (pin "2") (pinfunction "2_2") (pintype "passive"))
    )
    (net (code "72") (name "Net-(E1Q-IO38)") (class "Default")
      (node (ref "E1") (pin "48") (pinfunction "IO38_48") (pintype "bidirectional"))
      (node (ref "W4W3") (pin "2") (pinfunction "2_2") (pintype "passive"))
    )
    (net (code "73") (name "Net-(E1Q-IO41)") (class "Default")
      (node (ref "E1") (pin "51") (pinfunction "IO41_51") (pintype "bidirectional"))
      (node (ref "W4W3") (pin "3") (pinfunction "3_3") (pintype "passive"))
    )
    (net (code "74") (name "Net-(E1Q-IO61)") (class "Default")
      (node (ref "E1") (pin "77") (pinfunction "IO61_77") (pintype "bidirectional"))
      (node (ref "Q1") (pin "3") (pinfunction "C_3") (pintype "passive"))
      (node (ref "R27") (pin "1") (pinfunction "1_1") (pintype "passive"))
    )
    (net (code "75") (name "Net-(E04A-C)") (class "Default")
      (node (ref "C36") (pin "-") (pinfunction "-_-") (pintype "passive"))
      (node (ref "E04") (pin "14") (pinfunction "C_14") (pintype "input"))
    )
    (net (code "76") (name "Net-(E04A-CLR)") (class "Default")
      (node (ref "E04") (pin "3") (pinfunction "CLR_3") (pintype "input"))
      (node (ref "E1") (pin "85") (pinfunction "IO69_85") (pintype "bidirectional"))
      (node (ref "R42") (pin "2") (pinfunction "2_2") (pintype "passive"))
    )
    (net (code "77") (name "Net-(E04A-R{slash}C)") (class "Default")
      (node (ref "C36") (pin "+") (pinfunction "+_+") (pintype "passive"))
      (node (ref "E04") (pin "15") (pinfunction "R/C_15") (pintype "input"))
      (node (ref "R17") (pin "1") (pinfunction "1_1") (pintype "passive"))
    )
    (net (code "78") (name "Net-(E04A-~{Q})") (class "Default")
      (node (ref "E04") (pin "4") (pinfunction "~{Q}_4") (pintype "output"))
      (node (ref "E1") (pin "87") (pinfunction "IO/GCLK3_87") (pintype "bidirectional"))
    )
    (net (code "79") (name "Net-(E04B-B)") (class "Default")
      (node (ref "C40") (pin "1") (pinfunction "1_1") (pintype "passive"))
      (node (ref "E04") (pin "10") (pinfunction "B_10") (pintype "input"))
      (node (ref "R25") (pin "1") (pinfunction "1_1") (pintype "passive"))
    )
    (net (code "80") (name "Net-(E04B-C)") (class "Default")
      (node (ref "C39") (pin "2") (pinfunction "2_2") (pintype "passive"))
      (node (ref "E04") (pin "6") (pinfunction "C_6") (pintype "input"))
    )
    (net (code "81") (name "Net-(E04B-R{slash}C)") (class "Default")
      (node (ref "C39") (pin "1") (pinfunction "1_1") (pintype "passive"))
      (node (ref "E04") (pin "7") (pinfunction "R/C_7") (pintype "input"))
      (node (ref "R43") (pin "1") (pinfunction "1_1") (pintype "passive"))
    )
    (net (code "82") (name "Net-(E04B-~{Q})") (class "Default")
      (node (ref "E04") (pin "12") (pinfunction "~{Q}_12") (pintype "output"))
      (node (ref "R25") (pin "2") (pinfunction "2_2") (pintype "passive"))
    )
    (net (code "83") (name "Net-(E08A-B)") (class "Default")
      (node (ref "E08") (pin "2") (pinfunction "B_2") (pintype "input"))
      (node (ref "E08") (pin "5") (pinfunction "Q_5") (pintype "output"))
    )
    (net (code "84") (name "Net-(E08A-C)") (class "Default")
      (node (ref "C38") (pin "2") (pinfunction "2_2") (pintype "passive"))
      (node (ref "E08") (pin "14") (pinfunction "C_14") (pintype "input"))
    )
    (net (code "85") (name "Net-(E08A-CLR)") (class "Default")
      (node (ref "E08") (pin "11") (pinfunction "CLR_11") (pintype "input"))
      (node (ref "E08") (pin "3") (pinfunction "CLR_3") (pintype "input"))
      (node (ref "E1") (pin "92") (pinfunction "IN/GCLK2/OE2_92") (pintype "input"))
      (node (ref "R22") (pin "2") (pinfunction "2_2") (pintype "passive"))
    )
    (net (code "86") (name "Net-(E08A-R{slash}C)") (class "Default")
      (node (ref "C38") (pin "1") (pinfunction "1_1") (pintype "passive"))
      (node (ref "E08") (pin "15") (pinfunction "R/C_15") (pintype "input"))
      (node (ref "R24") (pin "1") (pinfunction "1_1") (pintype "passive"))
    )
    (net (code "87") (name "Net-(E08B-C)") (class "Default")
      (node (ref "C37") (pin "2") (pinfunction "2_2") (pintype "passive"))
      (node (ref "E08") (pin "6") (pinfunction "C_6") (pintype "input"))
    )
    (net (code "88") (name "Net-(E08B-R{slash}C)") (class "Default")
      (node (ref "C37") (pin "1") (pinfunction "1_1") (pintype "passive"))
      (node (ref "E08") (pin "7") (pinfunction "R/C_7") (pintype "input"))
      (node (ref "R23") (pin "1") (pinfunction "1_1") (pintype "passive"))
    )
    (net (code "89") (name "Net-(E08B-~{Q})") (class "Default")
      (node (ref "E08") (pin "12") (pinfunction "~{Q}_12") (pintype "output"))
      (node (ref "E1") (pin "91") (pinfunction "IN/GCLR_91") (pintype "input"))
    )
    (net (code "90") (name "Net-(Q1-B)") (class "Default")
      (node (ref "D1") (pin "C") (pinfunction "C_C") (pintype "passive"))
      (node (ref "Q1") (pin "2") (pinfunction "B_2") (pintype "passive"))
      (node (ref "R48") (pin "2") (pinfunction "2_2") (pintype "passive"))
    )
    (net (code "91") (name "Net-(Q1-E)") (class "Default")
      (node (ref "D5") (pin "C") (pinfunction "C_C") (pintype "passive"))
      (node (ref "Q1") (pin "1") (pinfunction "E_1") (pintype "passive"))
      (node (ref "R41") (pin "2") (pinfunction "2_2") (pintype "passive"))
    )
    (net (code "92") (name "Net-(Q2-E)") (class "Default")
      (node (ref "D9A") (pin "A") (pinfunction "A_A") (pintype "passive"))
      (node (ref "Q2") (pin "1") (pinfunction "E_1") (pintype "passive"))
    )
    (net (code "93") (name "Net-(Q3-E)") (class "Default")
      (node (ref "D9") (pin "A") (pinfunction "A_A") (pintype "passive"))
      (node (ref "Q3") (pin "1") (pinfunction "E_1") (pintype "passive"))
    )
    (net (code "94") (name "Net-(Q4-E)") (class "Default")
      (node (ref "D7") (pin "A") (pinfunction "A_A") (pintype "passive"))
      (node (ref "Q4") (pin "1") (pinfunction "E_1") (pintype "passive"))
    )
    (net (code "95") (name "Net-(Q5-E)") (class "Default")
      (node (ref "D10") (pin "A") (pinfunction "A_A") (pintype "passive"))
      (node (ref "Q5") (pin "1") (pinfunction "E_1") (pintype "passive"))
    )
    (net (code "96") (name "Net-(R26-A)") (class "Default")
      (node (ref "R26") (pin "1") (pinfunction "A_1") (pintype "passive"))
      (node (ref "R43") (pin "2") (pinfunction "2_2") (pintype "passive"))
    )
    (net (code "97") (name "VCC") (class "Default")
      (node (ref "C1") (pin "1") (pinfunction "1_1") (pintype "passive"))
      (node (ref "C2") (pin "1") (pinfunction "1_1") (pintype "passive"))
      (node (ref "C3") (pin "1") (pinfunction "1_1") (pintype "passive"))
      (node (ref "C4") (pin "1") (pinfunction "1_1") (pintype "passive"))
      (node (ref "C5") (pin "1") (pinfunction "1_1") (pintype "passive"))
      (node (ref "C6") (pin "+") (pinfunction "+_+") (pintype "passive"))
      (node (ref "C7") (pin "+") (pinfunction "+_+") (pintype "passive"))
      (node (ref "C8") (pin "+") (pinfunction "+_+") (pintype "passive"))
      (node (ref "E1") (pin "20") (pinfunction "VCCIO_20") (pintype "power_in"))
      (node (ref "E1") (pin "36") (pinfunction "VCCIO_36") (pintype "power_in"))
      (node (ref "E1") (pin "41") (pinfunction "VCCINT_41") (pintype "power_in"))
      (node (ref "E1") (pin "5") (pinfunction "VCCIO_5") (pintype "power_in"))
      (node (ref "E1") (pin "53") (pinfunction "VCCIO_53") (pintype "power_in"))
      (node (ref "E1") (pin "68") (pinfunction "VCCIO_68") (pintype "power_in"))
      (node (ref "E1") (pin "84") (pinfunction "VCCIO_84") (pintype "power_in"))
      (node (ref "E1") (pin "90") (pinfunction "IN/OE1_90") (pintype "input"))
      (node (ref "E1") (pin "93") (pinfunction "VCCINT_93") (pintype "power_in"))
      (node (ref "E25") (pin "14") (pinfunction "14_14") (pintype "passive"))
      (node (ref "EDGE$3") (pin "AA2") (pinfunction "1_AA2") (pintype "bidirectional"))
      (node (ref "EDGE$3") (pin "BA2") (pinfunction "1_BA2") (pintype "bidirectional"))
      (node (ref "EDGE$3") (pin "CA2") (pinfunction "1_CA2") (pintype "bidirectional"))
      (node (ref "ISP") (pin "4") (pinfunction "4_4") (pintype "passive"))
      (node (ref "R1") (pin "2") (pinfunction "2_2") (pintype "passive"))
      (node (ref "R11") (pin "2") (pinfunction "2_2") (pintype "passive"))
      (node (ref "R16") (pin "2") (pinfunction "2_2") (pintype "passive"))
      (node (ref "R17") (pin "2") (pinfunction "2_2") (pintype "passive"))
      (node (ref "R18") (pin "2") (pinfunction "2_2") (pintype "passive"))
      (node (ref "R22") (pin "1") (pinfunction "1_1") (pintype "passive"))
      (node (ref "R23") (pin "2") (pinfunction "2_2") (pintype "passive"))
      (node (ref "R24") (pin "2") (pinfunction "2_2") (pintype "passive"))
      (node (ref "R26") (pin "2") (pinfunction "S_2") (pintype "passive"))
      (node (ref "R26") (pin "3") (pinfunction "E_3") (pintype "passive"))
      (node (ref "R27") (pin "2") (pinfunction "2_2") (pintype "passive"))
      (node (ref "R4") (pin "2") (pinfunction "2_2") (pintype "passive"))
      (node (ref "R42") (pin "1") (pinfunction "1_1") (pintype "passive"))
      (node (ref "R5") (pin "2") (pinfunction "2_2") (pintype "passive"))
      (node (ref "R7") (pin "2") (pinfunction "2_2") (pintype "passive"))
    )
    (net (code "98") (name "unconnected-(E1Q-IO39-Pad49)") (class "Default")
      (node (ref "E1") (pin "49") (pinfunction "IO39_49") (pintype "bidirectional"))
    )
    (net (code "99") (name "unconnected-(E1Q-IO40-Pad50)") (class "Default")
      (node (ref "E1") (pin "50") (pinfunction "IO40_50") (pintype "bidirectional"))
    )
    (net (code "100") (name "unconnected-(E1Q-IO43-Pad54)") (class "Default")
      (node (ref "E1") (pin "54") (pinfunction "IO43_54") (pintype "bidirectional"))
    )
    (net (code "101") (name "unconnected-(E1Q-IO44-Pad55)") (class "Default")
      (node (ref "E1") (pin "55") (pinfunction "IO44_55") (pintype "bidirectional"))
    )
    (net (code "102") (name "unconnected-(E1Q-IO45-Pad56)") (class "Default")
      (node (ref "E1") (pin "56") (pinfunction "IO45_56") (pintype "bidirectional"))
    )
    (net (code "103") (name "unconnected-(E1Q-IO47-Pad58)") (class "Default")
      (node (ref "E1") (pin "58") (pinfunction "IO47_58") (pintype "bidirectional"))
    )
    (net (code "104") (name "unconnected-(E1Q-IO48-Pad59)") (class "Default")
      (node (ref "E1") (pin "59") (pinfunction "IO48_59") (pintype "bidirectional"))
    )
    (net (code "105") (name "unconnected-(E1Q-IO49-Pad60)") (class "Default")
      (node (ref "E1") (pin "60") (pinfunction "IO49_60") (pintype "bidirectional"))
    )
    (net (code "106") (name "unconnected-(E1Q-IO50-Pad62)") (class "Default")
      (node (ref "E1") (pin "62") (pinfunction "IO50_62") (pintype "bidirectional"))
    )
    (net (code "107") (name "unconnected-(E1Q-IO51-Pad63)") (class "Default")
      (node (ref "E1") (pin "63") (pinfunction "IO51_63") (pintype "bidirectional"))
    )
    (net (code "108") (name "unconnected-(E1Q-IO52-Pad65)") (class "Default")
      (node (ref "E1") (pin "65") (pinfunction "IO52_65") (pintype "bidirectional"))
    )
    (net (code "109") (name "unconnected-(E1Q-IO53-Pad66)") (class "Default")
      (node (ref "E1") (pin "66") (pinfunction "IO53_66") (pintype "bidirectional"))
    )
    (net (code "110") (name "unconnected-(E1Q-IO54-Pad67)") (class "Default")
      (node (ref "E1") (pin "67") (pinfunction "IO54_67") (pintype "bidirectional"))
    )
    (net (code "111") (name "unconnected-(E1Q-IO55-Pad69)") (class "Default")
      (node (ref "E1") (pin "69") (pinfunction "IO55_69") (pintype "bidirectional"))
    )
    (net (code "112") (name "unconnected-(E1Q-IO70-Pad86)") (class "Default")
      (node (ref "E1") (pin "86") (pinfunction "IO70_86") (pintype "bidirectional"))
    )
    (net (code "113") (name "unconnected-(E1Q-IO71-Pad94)") (class "Default")
      (node (ref "E1") (pin "94") (pinfunction "IO71_94") (pintype "bidirectional"))
    )
    (net (code "114") (name "unconnected-(E1Q-IO{slash}PD2-Pad43)") (class "Default")
      (node (ref "E1") (pin "43") (pinfunction "IO/PD2_43") (pintype "bidirectional"))
    )
    (net (code "115") (name "unconnected-(E04A-Q-Pad13)") (class "Default")
      (node (ref "E04") (pin "13") (pinfunction "Q_13") (pintype "output"))
    )
    (net (code "116") (name "unconnected-(E08A-~{Q}-Pad4)") (class "Default")
      (node (ref "E08") (pin "4") (pinfunction "~{Q}_4") (pintype "output"))
    )
    (net (code "117") (name "unconnected-(E25-Pad1)") (class "Default")
      (node (ref "E25") (pin "1") (pinfunction "1_1") (pintype "passive"))
    )
    (net (code "118") (name "unconnected-(E25-Pad2)") (class "Default")
      (node (ref "E25") (pin "2") (pinfunction "2_2") (pintype "passive"))
    )
    (net (code "119") (name "unconnected-(E25-Pad3)") (class "Default")
      (node (ref "E25") (pin "3") (pinfunction "3_3") (pintype "passive"))
    )
    (net (code "120") (name "unconnected-(E25-Pad4)") (class "Default")
      (node (ref "E25") (pin "4") (pinfunction "4_4") (pintype "passive"))
    )
    (net (code "121") (name "unconnected-(E25-Pad5)") (class "Default")
      (node (ref "E25") (pin "5") (pinfunction "5_5") (pintype "passive"))
    )
    (net (code "122") (name "unconnected-(E25-Pad6)") (class "Default")
      (node (ref "E25") (pin "6") (pinfunction "6_6") (pintype "passive"))
    )
    (net (code "123") (name "unconnected-(E25-Pad8)") (class "Default")
      (node (ref "E25") (pin "8") (pinfunction "8_8") (pintype "passive"))
    )
    (net (code "124") (name "unconnected-(E25-Pad9)") (class "Default")
      (node (ref "E25") (pin "9") (pinfunction "9_9") (pintype "passive"))
    )
    (net (code "125") (name "unconnected-(E25-Pad10)") (class "Default")
      (node (ref "E25") (pin "10") (pinfunction "10_10") (pintype "passive"))
    )
    (net (code "126") (name "unconnected-(E25-Pad11)") (class "Default")
      (node (ref "E25") (pin "11") (pinfunction "11_11") (pintype "passive"))
    )
    (net (code "127") (name "unconnected-(E25-Pad12)") (class "Default")
      (node (ref "E25") (pin "12") (pinfunction "12_12") (pintype "passive"))
    )
    (net (code "128") (name "unconnected-(E25-Pad13)") (class "Default")
      (node (ref "E25") (pin "13") (pinfunction "13_13") (pintype "passive"))
    )
    (net (code "129") (name "unconnected-(ISP-Pad6)") (class "Default")
      (node (ref "ISP") (pin "6") (pinfunction "6_6") (pintype "passive"))
    )
    (net (code "130") (name "unconnected-(ISP-Pad7)") (class "Default")
      (node (ref "ISP") (pin "7") (pinfunction "7_7") (pintype "passive"))
    )
    (net (code "131") (name "unconnected-(ISP-Pad8)") (class "Default")
      (node (ref "ISP") (pin "8") (pinfunction "8_8") (pintype "passive"))
    )
    (net (code "132") (name "unconnected-(J1-14-PadR)") (class "Default")
      (node (ref "J1") (pin "R") (pinfunction "14_R") (pintype "bidirectional"))
    )
  )
)
